# P01_BCS1_Power_BBCore.net
KiCad netlist of a schematic drawn in Altium Designer
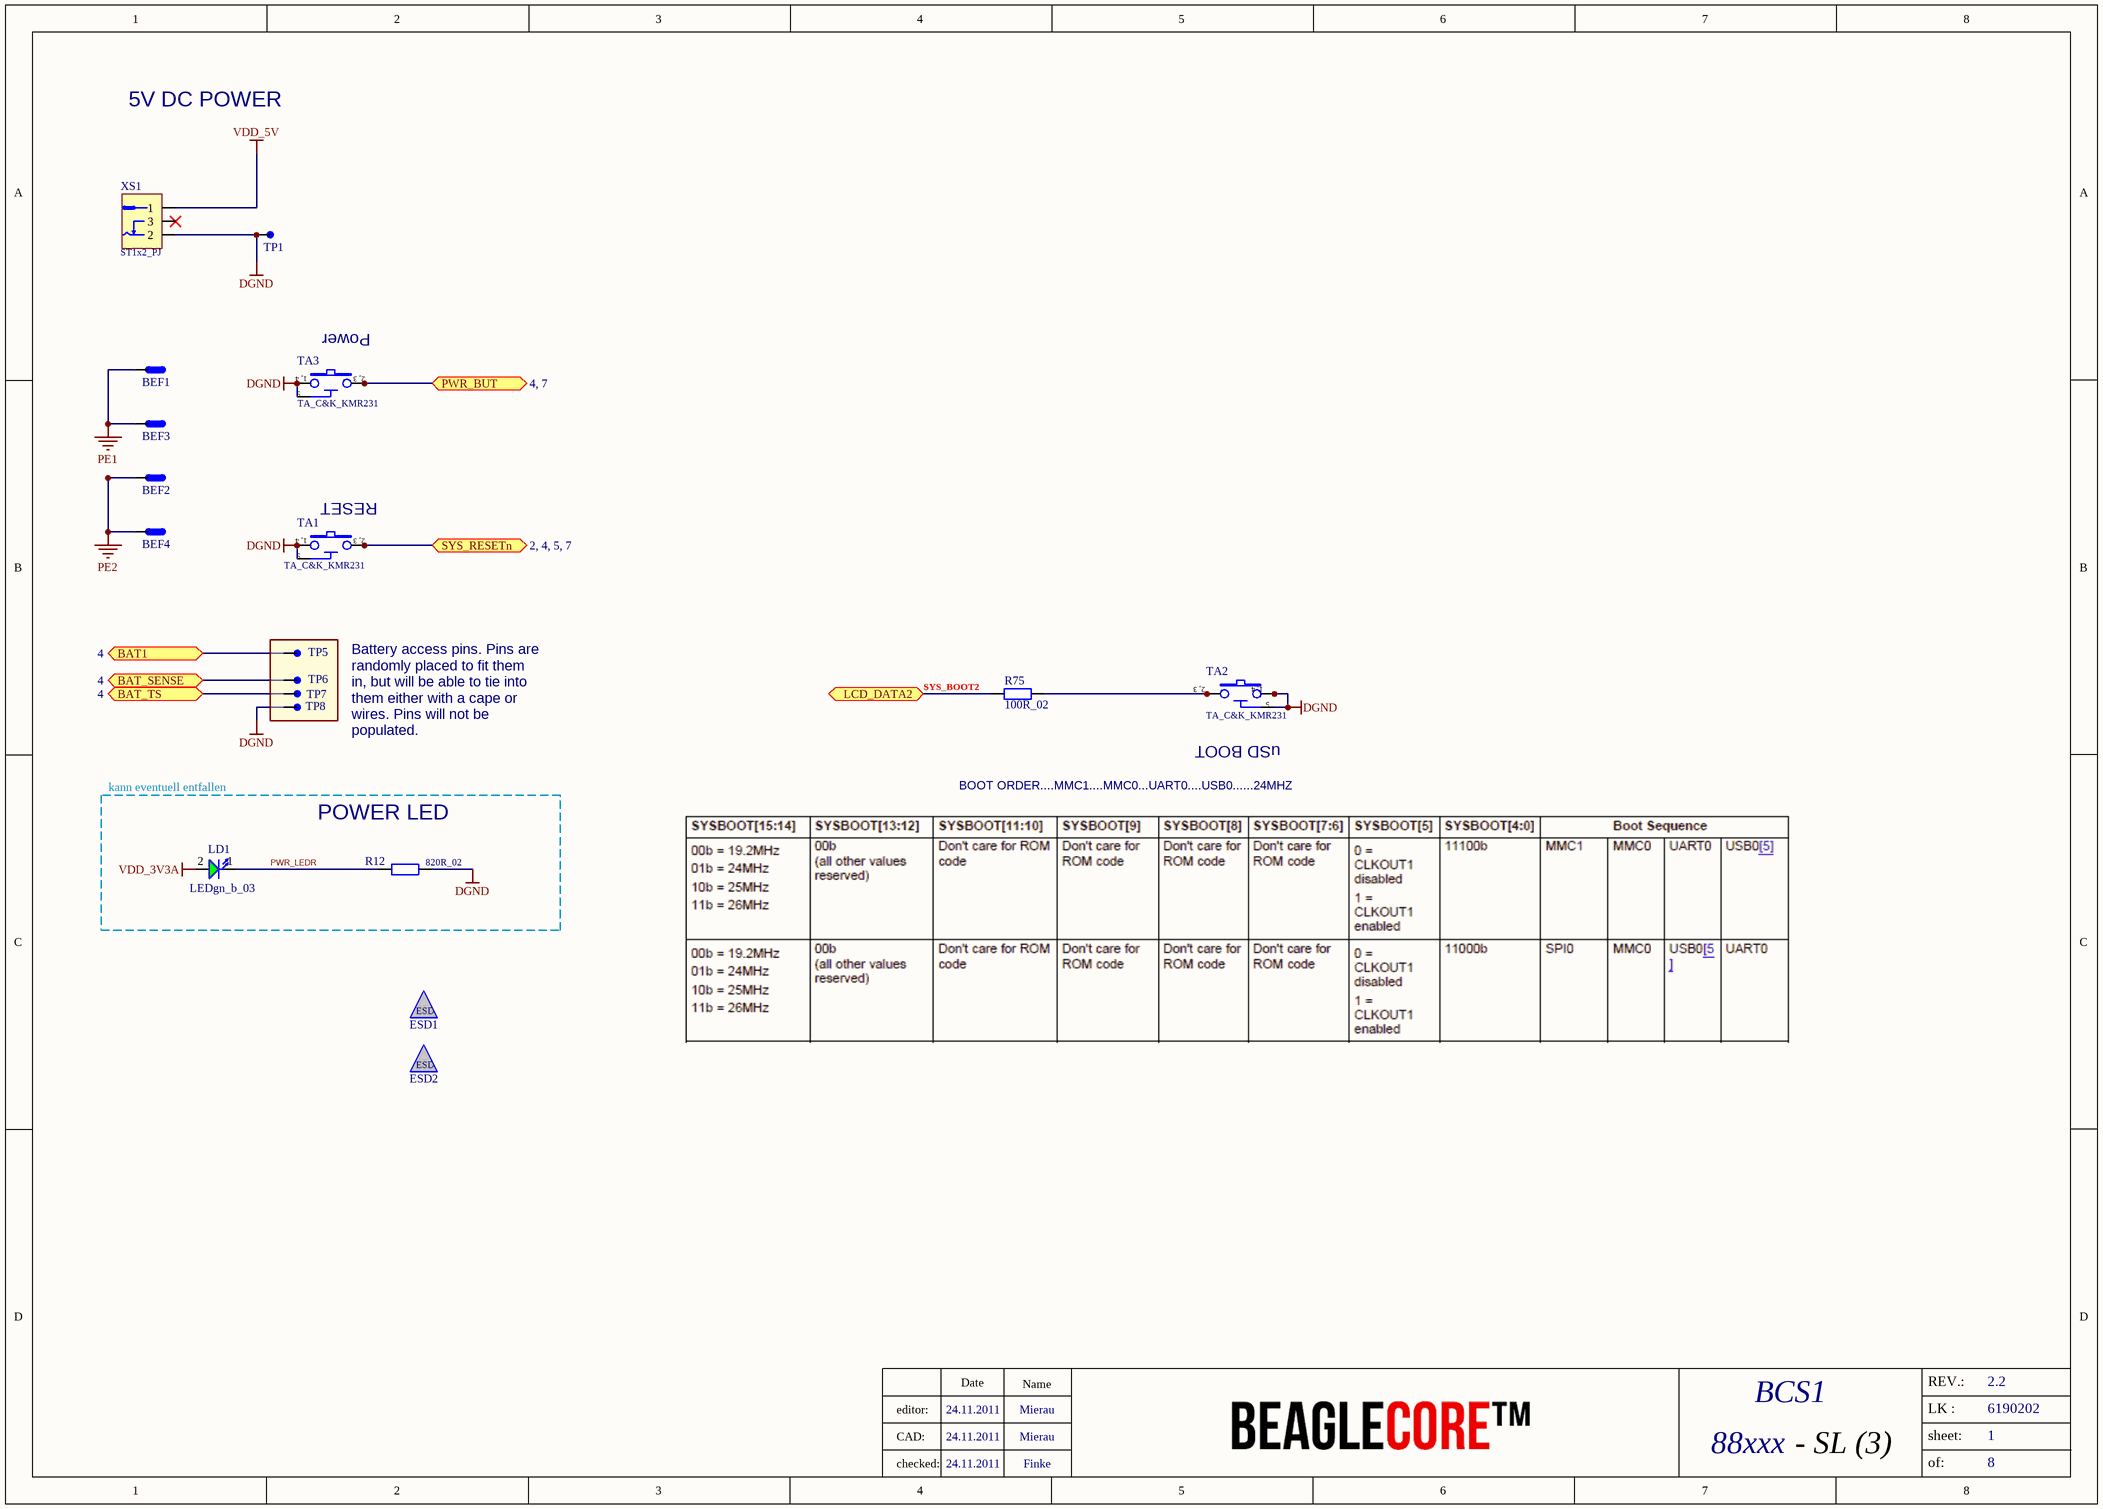
[diagram p0: P01_BCS1_Power BBCore.SchDoc]

(export (version "E")
  (design (tool "Eeschema 10.0.6"))
  (components
    (comp (ref "BEF1")
      (value "BEF_3.2_4.45")
      (footprint "BEF_3.2_4.45")
      (description "Befestigungsbohrung D=3.2mm_4.45_Rand")
      (libsource (lib "*") (part "A_BEF_3.2_4.45"))
    )
    (comp (ref "BEF2")
      (value "BEF_3.2_4.45")
      (footprint "BEF_3.2_4.45")
      (description "Befestigungsbohrung D=3.2mm_4.45_Rand")
      (libsource (lib "*") (part "A_BEF_3.2_4.45"))
    )
    (comp (ref "BEF3")
      (value "BEF_3.2_4.45")
      (footprint "BEF_3.2_4.45")
      (description "Befestigungsbohrung D=3.2mm_4.45_Rand")
      (libsource (lib "*") (part "A_BEF_3.2_4.45"))
    )
    (comp (ref "BEF4")
      (value "BEF_3.2_4.45")
      (footprint "BEF_3.2_4.45")
      (description "Befestigungsbohrung D=3.2mm_4.45_Rand")
      (libsource (lib "*") (part "A_BEF_3.2_4.45"))
    )
    (comp (ref "ESD1")
      (value "ESD")
      (footprint "ESD_G")
      (description "ESD Symbol")
      (libsource (lib "*") (part "A_ESD"))
    )
    (comp (ref "ESD2")
      (value "ESD")
      (footprint "ESD_G")
      (description "ESD Symbol")
      (libsource (lib "*") (part "A_ESD"))
    )
    (comp (ref "LD1")
      (value "LEDgn_b_03")
      (footprint "CD1608-0603")
      (description "Leuchtdiode bright grün 0603, RV(5mA)@3V3= 100OHM")
      (libsource (lib "*") (part "LD_LEDgn_bright_03"))
    )
    (comp (ref "R12")
      (value "820R_02")
      (footprint "CR1005-0402")
      (description "Resistor 0402")
      (libsource (lib "*") (part "R820R_02"))
    )
    (comp (ref "R75")
      (value "100R_02")
      (footprint "CR1005-0402")
      (description "Resistor 0402 1%")
      (libsource (lib "*") (part "R100R_02"))
    )
    (comp (ref "TA1")
      (value "TA_C&K_KMR231")
      (footprint "TA_KMR2")
      (description "Taster smd 1pol mm pitch, 4.6x2.8mm case")
      (libsource (lib "*") (part "TASTER_C&K_KMR231"))
    )
    (comp (ref "TA2")
      (value "TA_C&K_KMR231")
      (footprint "TA_KMR2")
      (description "Taster smd 1pol mm pitch, 4.6x2.8mm case")
      (libsource (lib "*") (part "TASTER_C&K_KMR231"))
    )
    (comp (ref "TA3")
      (value "TA_C&K_KMR231")
      (footprint "TA_KMR2")
      (description "Taster smd 1pol mm pitch, 4.6x2.8mm case")
      (libsource (lib "*") (part "TASTER_C&K_KMR231"))
    )
    (comp (ref "TP1")
      (value "TP THT")
      (footprint "TP mit 0.8mm Bohrung")
      (description "Testpunkt rund mit Bohrung D=0.8mm")
      (libsource (lib "*") (part "TP1.6 mit Bohrung 0.8"))
    )
    (comp (ref "TP5")
      (value "TP THT")
      (footprint "TP mit 0.8mm Bohrung")
      (description "Testpunkt rund mit Bohrung D=0.8mm")
      (libsource (lib "*") (part "TP1.6 mit Bohrung 0.8"))
    )
    (comp (ref "TP6")
      (value "TP THT")
      (footprint "TP mit 0.8mm Bohrung")
      (description "Testpunkt rund mit Bohrung D=0.8mm")
      (libsource (lib "*") (part "TP1.6 mit Bohrung 0.8"))
    )
    (comp (ref "TP7")
      (value "TP THT")
      (footprint "TP mit 0.8mm Bohrung")
      (description "Testpunkt rund mit Bohrung D=0.8mm")
      (libsource (lib "*") (part "TP1.6 mit Bohrung 0.8"))
    )
    (comp (ref "TP8")
      (value "TP THT")
      (footprint "TP mit 0.8mm Bohrung")
      (description "Testpunkt rund mit Bohrung D=0.8mm")
      (libsource (lib "*") (part "TP1.6 mit Bohrung 0.8"))
    )
    (comp (ref "XS1")
      (value "ST1x2_PJ")
      (footprint "ST1X2THT-2mm-DC_WA")
      (description "DC-Power-Jack, 2mm Stift, 5A, THT,gew.")
      (libsource (lib "*") (part "XST1X2_PJ_WA"))
    )
  )
  (nets
    (net (code "1") (name "/BAT1") (class "Default")
      (node (ref "TP5") (pin "1") (pinfunction "Pin_1") (pintype "passive"))
    )
    (net (code "2") (name "/BAT_SENSE") (class "Default")
      (node (ref "TP6") (pin "1") (pinfunction "Pin_1") (pintype "passive"))
    )
    (net (code "3") (name "/BAT_TS") (class "Default")
      (node (ref "TP7") (pin "1") (pinfunction "Pin_1") (pintype "passive"))
    )
    (net (code "4") (name "/LCD_DATA2") (class "Default")
      (node (ref "R75") (pin "1") (pinfunction "1_1") (pintype "passive"))
    )
    (net (code "5") (name "/PWR_BUT") (class "Default")
      (node (ref "TA3") (pin "2") (pinfunction "2_2") (pintype "passive"))
      (node (ref "TA3") (pin "3") (pinfunction "3_3") (pintype "passive"))
    )
    (net (code "6") (name "/PWR_LEDR") (class "Default")
      (node (ref "LD1") (pin "1") (pinfunction "K_1") (pintype "passive"))
      (node (ref "R12") (pin "1") (pinfunction "1_1") (pintype "passive"))
    )
    (net (code "7") (name "/SYS_RESETn") (class "Default")
      (node (ref "TA1") (pin "2") (pinfunction "2_2") (pintype "passive"))
      (node (ref "TA1") (pin "3") (pinfunction "3_3") (pintype "passive"))
    )
    (net (code "8") (name "DGND") (class "Default")
      (node (ref "R12") (pin "2") (pinfunction "2_2") (pintype "passive"))
      (node (ref "TA1") (pin "1") (pinfunction "1_1") (pintype "passive"))
      (node (ref "TA1") (pin "4") (pinfunction "4_4") (pintype "passive"))
      (node (ref "TA1") (pin "5") (pinfunction "5_5") (pintype "passive"))
      (node (ref "TA2") (pin "1") (pinfunction "1_1") (pintype "passive"))
      (node (ref "TA2") (pin "4") (pinfunction "4_4") (pintype "passive"))
      (node (ref "TA2") (pin "5") (pinfunction "5_5") (pintype "passive"))
      (node (ref "TA3") (pin "1") (pinfunction "1_1") (pintype "passive"))
      (node (ref "TA3") (pin "4") (pinfunction "4_4") (pintype "passive"))
      (node (ref "TA3") (pin "5") (pinfunction "5_5") (pintype "passive"))
      (node (ref "TP1") (pin "1") (pinfunction "Pin_1") (pintype "passive"))
      (node (ref "TP8") (pin "1") (pinfunction "Pin_1") (pintype "passive"))
      (node (ref "XS1") (pin "2") (pinfunction "2_2") (pintype "passive"))
    )
    (net (code "9") (name "Net-(R75-Pad2)") (class "Default")
      (node (ref "R75") (pin "2") (pinfunction "2_2") (pintype "passive"))
      (node (ref "TA2") (pin "2") (pinfunction "2_2") (pintype "passive"))
      (node (ref "TA2") (pin "3") (pinfunction "3_3") (pintype "passive"))
    )
    (net (code "10") (name "PE1") (class "Default")
      (node (ref "BEF1") (pin "1") (pinfunction "Pin_1") (pintype "passive"))
      (node (ref "BEF3") (pin "1") (pinfunction "Pin_1") (pintype "passive"))
    )
    (net (code "11") (name "PE2") (class "Default")
      (node (ref "BEF2") (pin "1") (pinfunction "Pin_1") (pintype "passive"))
      (node (ref "BEF4") (pin "1") (pinfunction "Pin_1") (pintype "passive"))
    )
    (net (code "12") (name "VDD_3V3A") (class "Default")
      (node (ref "LD1") (pin "2") (pinfunction "A_2") (pintype "passive"))
    )
    (net (code "13") (name "VDD_5V") (class "Default")
      (node (ref "XS1") (pin "1") (pinfunction "1_1") (pintype "passive"))
    )
    (net (code "14") (name "unconnected-(XS1-Pad3)") (class "Default")
      (node (ref "XS1") (pin "3") (pinfunction "3_3") (pintype "passive+no_connect"))
    )
  )
)
